# main.net
KiCad netlist of a schematic drawn in EAGLE
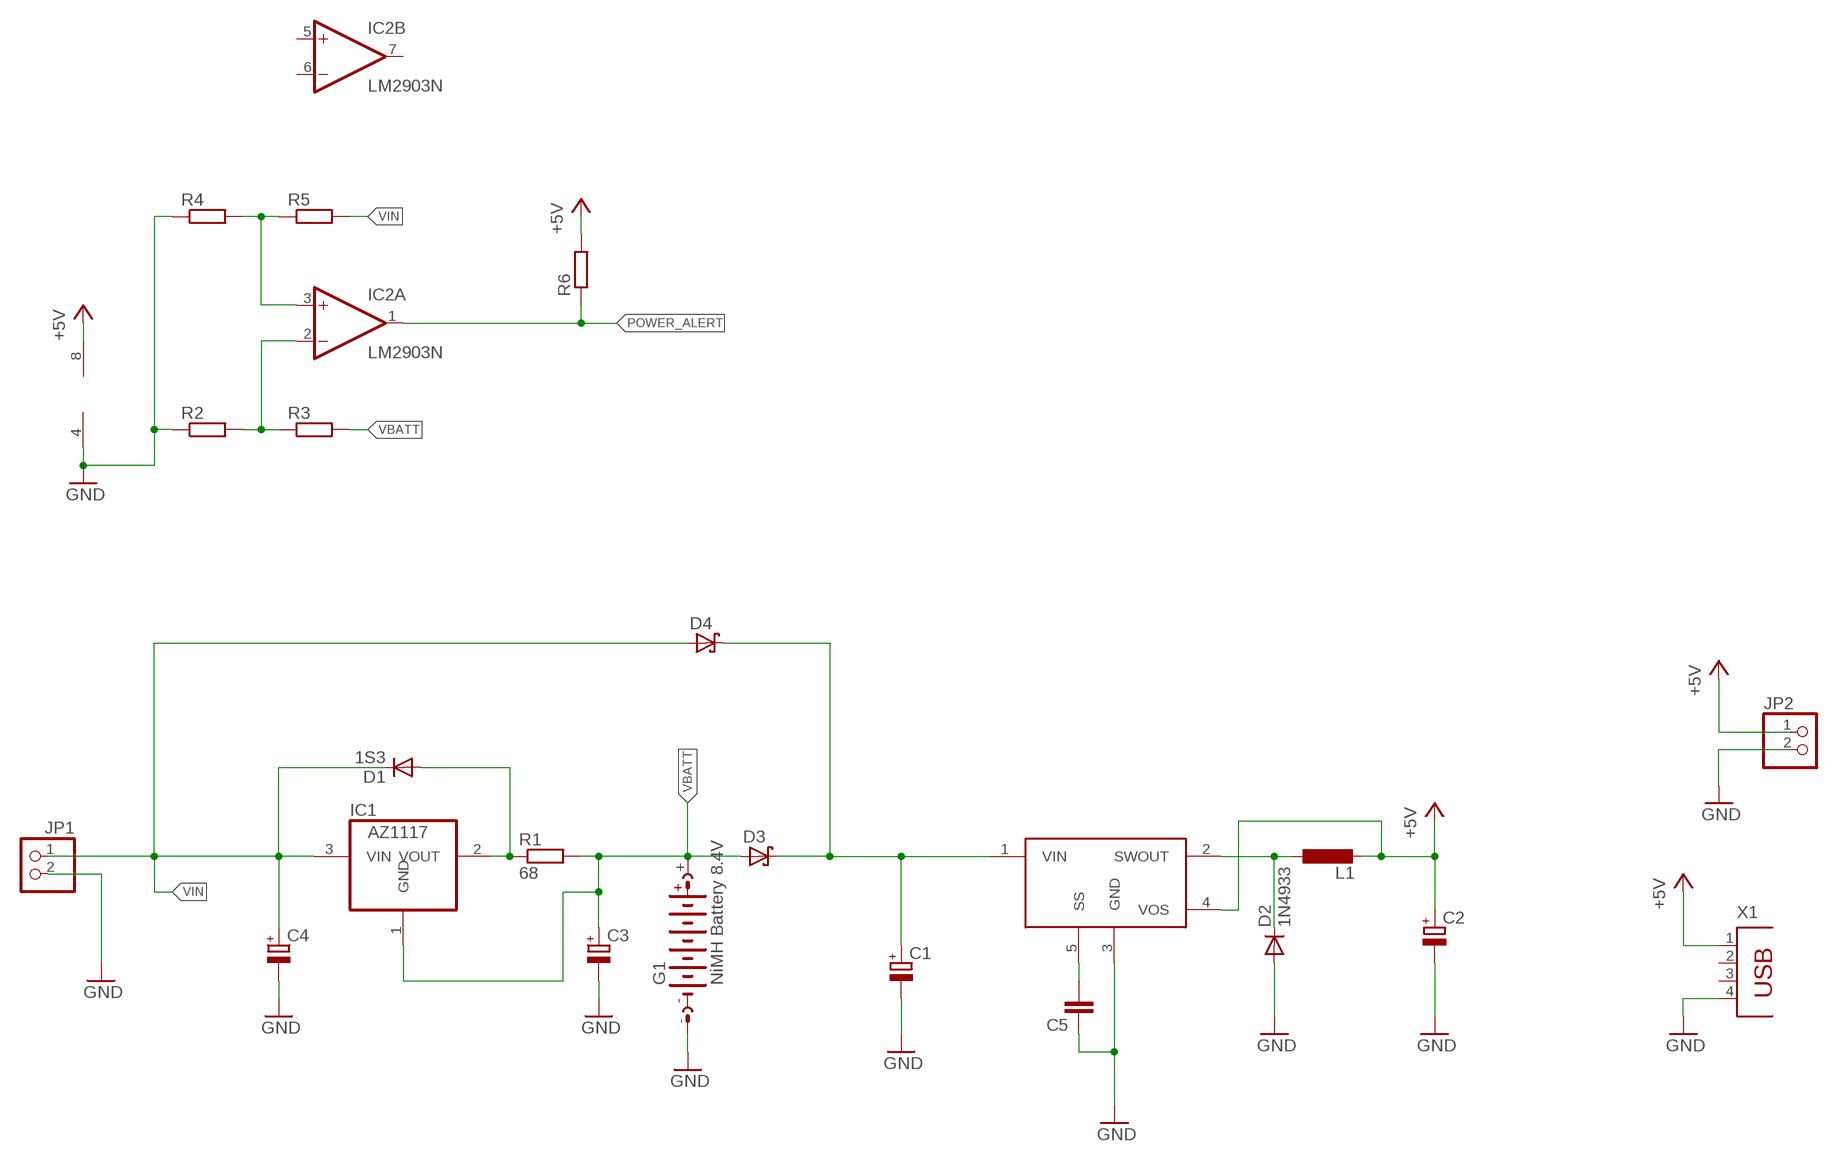
[diagram p0: schematic, sheet 1]

(export (version "E")
  (design (tool "Eeschema 10.0.6"))
  (components
    (comp (ref "C1")
      (value "CPOL-EUE5-10.5")
      (footprint "eagle-import:E5-10,5")
      (libsource (lib "eagle-import") (part "CPOL-EUE5-10.5"))
    )
    (comp (ref "C2")
      (value "CPOL-EUE5-10.5")
      (footprint "eagle-import:E5-10,5")
      (libsource (lib "eagle-import") (part "CPOL-EUE5-10.5"))
    )
    (comp (ref "C3")
      (value "CPOL-EUE5-10.5")
      (footprint "eagle-import:E5-10,5")
      (libsource (lib "eagle-import") (part "CPOL-EUE5-10.5"))
    )
    (comp (ref "C4")
      (value "CPOL-EUE5-10.5")
      (footprint "eagle-import:E5-10,5")
      (libsource (lib "eagle-import") (part "CPOL-EUE5-10.5"))
    )
    (comp (ref "C5")
      (value "C-EUC0603K")
      (footprint "eagle-import:C0603K")
      (libsource (lib "eagle-import") (part "C-EUC0603K"))
    )
    (comp (ref "D1")
      (value "1S3")
      (footprint "eagle-import:DO41-10")
      (libsource (lib "eagle-import") (part "1N4004"))
    )
    (comp (ref "D2")
      (value "1N4933")
      (footprint "eagle-import:DO41-10")
      (libsource (lib "eagle-import") (part "1N4933"))
    )
    (comp (ref "D3")
      (value "SCHOTTKY-DIODEC4111-15")
      (footprint "eagle-import:C4111-15")
      (libsource (lib "eagle-import") (part "SCHOTTKY-DIODEC4111-15"))
    )
    (comp (ref "D4")
      (value "SCHOTTKY-DIODEC4111-15")
      (footprint "eagle-import:C4111-15")
      (libsource (lib "eagle-import") (part "SCHOTTKY-DIODEC4111-15"))
    )
    (comp (ref "G1")
      (value "NiMH Battery 8.4V")
      (footprint "eagle-import:AB9V")
      (libsource (lib "eagle-import") (part "AB9V"))
    )
    (comp (ref "IC1")
      (value "AZ1117")
      (footprint "eagle-import:SOT223")
      (fields (field (name "MPN") "REG1117"))
      (libsource (lib "eagle-import") (part "REG1117"))
    )
    (comp (ref "IC2")
      (value "LM2903N")
      (footprint "eagle-import:DIL08")
      (libsource (lib "eagle-import") (part "LM2903N"))
    )
    (comp (ref "JP1")
      (value "PINHD-1X2")
      (footprint "eagle-import:1X02")
      (libsource (lib "eagle-import") (part "PINHD-1X2"))
    )
    (comp (ref "JP2")
      (value "PINHD-1X2")
      (footprint "eagle-import:1X02")
      (libsource (lib "eagle-import") (part "PINHD-1X2"))
    )
    (comp (ref "L1")
      (value "L-EU0207/10")
      (footprint "eagle-import:0207_10")
      (libsource (lib "eagle-import") (part "L-EU0207/10"))
    )
    (comp (ref "R1")
      (value "68")
      (footprint "eagle-import:0207_12")
      (libsource (lib "eagle-import") (part "R-EU_0207/12"))
    )
    (comp (ref "R2")
      (value "R-EU_R0603")
      (footprint "eagle-import:R0603")
      (libsource (lib "eagle-import") (part "R-EU_R0603"))
    )
    (comp (ref "R3")
      (value "R-EU_R0603")
      (footprint "eagle-import:R0603")
      (libsource (lib "eagle-import") (part "R-EU_R0603"))
    )
    (comp (ref "R4")
      (value "R-EU_R0603")
      (footprint "eagle-import:R0603")
      (libsource (lib "eagle-import") (part "R-EU_R0603"))
    )
    (comp (ref "R5")
      (value "R-EU_R0603")
      (footprint "eagle-import:R0603")
      (libsource (lib "eagle-import") (part "R-EU_R0603"))
    )
    (comp (ref "R6")
      (value "R-EU_R0603")
      (footprint "eagle-import:R0603")
      (libsource (lib "eagle-import") (part "R-EU_R0603"))
    )
    (comp (ref "U$1")
      (value "SI-8050S")
      (footprint "eagle-import:TO220-5")
      (libsource (lib "eagle-import") (part "SI-8050S"))
    )
    (comp (ref "X1")
      (value "PN87520")
      (footprint "eagle-import:PN87520")
      (libsource (lib "eagle-import") (part "PN87520"))
    )
  )
  (nets
    (net (code "1") (name "+5V") (class "Default")
      (node (ref "C2") (pin "+") (pinfunction "+_+") (pintype "passive"))
      (node (ref "IC2") (pin "8") (pinfunction "V+_8") (pintype "power_in"))
      (node (ref "JP2") (pin "1") (pinfunction "1_1") (pintype "passive"))
      (node (ref "L1") (pin "2") (pinfunction "2_2") (pintype "passive"))
      (node (ref "R6") (pin "2") (pinfunction "2_2") (pintype "passive"))
      (node (ref "U$1") (pin "4") (pinfunction "VOS_4") (pintype "bidirectional"))
      (node (ref "X1") (pin "1") (pinfunction "1_1") (pintype "passive"))
    )
    (net (code "2") (name "GND") (class "Default")
      (node (ref "C1") (pin "-") (pinfunction "-_-") (pintype "passive"))
      (node (ref "C2") (pin "-") (pinfunction "-_-") (pintype "passive"))
      (node (ref "C3") (pin "-") (pinfunction "-_-") (pintype "passive"))
      (node (ref "C4") (pin "-") (pinfunction "-_-") (pintype "passive"))
      (node (ref "C5") (pin "1") (pinfunction "1_1") (pintype "passive"))
      (node (ref "D2") (pin "A") (pinfunction "A_A") (pintype "passive"))
      (node (ref "G1") (pin "-") (pinfunction "-_-") (pintype "passive"))
      (node (ref "IC2") (pin "4") (pinfunction "V-_4") (pintype "power_in"))
      (node (ref "JP1") (pin "2") (pinfunction "2_2") (pintype "passive"))
      (node (ref "JP2") (pin "2") (pinfunction "2_2") (pintype "passive"))
      (node (ref "R2") (pin "1") (pinfunction "1_1") (pintype "passive"))
      (node (ref "R4") (pin "1") (pinfunction "1_1") (pintype "passive"))
      (node (ref "U$1") (pin "3") (pinfunction "GND_3") (pintype "bidirectional"))
      (node (ref "X1") (pin "4") (pinfunction "4_4") (pintype "passive"))
    )
    (net (code "3") (name "Net-(IC1-VOUT)") (class "Default")
      (node (ref "D1") (pin "A") (pinfunction "A_A") (pintype "passive"))
      (node (ref "IC1") (pin "2") (pinfunction "VOUT_2") (pintype "output"))
      (node (ref "R1") (pin "1") (pinfunction "1_1") (pintype "passive"))
    )
    (net (code "4") (name "Net-(IC2A-+IN)") (class "Default")
      (node (ref "IC2") (pin "3") (pinfunction "+IN_3") (pintype "input"))
      (node (ref "R4") (pin "2") (pinfunction "2_2") (pintype "passive"))
      (node (ref "R5") (pin "1") (pinfunction "1_1") (pintype "passive"))
    )
    (net (code "5") (name "Net-(IC2A--IN)") (class "Default")
      (node (ref "IC2") (pin "2") (pinfunction "-IN_2") (pintype "input"))
      (node (ref "R2") (pin "2") (pinfunction "2_2") (pintype "passive"))
      (node (ref "R3") (pin "1") (pinfunction "1_1") (pintype "passive"))
    )
    (net (code "6") (name "Net-(U$1-SS)") (class "Default")
      (node (ref "C5") (pin "2") (pinfunction "2_2") (pintype "passive"))
      (node (ref "U$1") (pin "5") (pinfunction "SS_5") (pintype "bidirectional"))
    )
    (net (code "7") (name "Net-(U$1-SWOUT)") (class "Default")
      (node (ref "D2") (pin "C") (pinfunction "C_C") (pintype "passive"))
      (node (ref "L1") (pin "1") (pinfunction "1_1") (pintype "passive"))
      (node (ref "U$1") (pin "2") (pinfunction "SWOUT_2") (pintype "bidirectional"))
    )
    (net (code "8") (name "Net-(U$1-VIN)") (class "Default")
      (node (ref "C1") (pin "+") (pinfunction "+_+") (pintype "passive"))
      (node (ref "D3") (pin "C") (pinfunction "C_C") (pintype "passive"))
      (node (ref "D4") (pin "C") (pinfunction "C_C") (pintype "passive"))
      (node (ref "U$1") (pin "1") (pinfunction "VIN_1") (pintype "bidirectional"))
    )
    (net (code "9") (name "POWER_ALERT") (class "Default")
      (node (ref "IC2") (pin "1") (pinfunction "OUT_1") (pintype "output"))
      (node (ref "R6") (pin "1") (pinfunction "1_1") (pintype "passive"))
    )
    (net (code "10") (name "VBATT") (class "Default")
      (node (ref "C3") (pin "+") (pinfunction "+_+") (pintype "passive"))
      (node (ref "D3") (pin "A") (pinfunction "A_A") (pintype "passive"))
      (node (ref "G1") (pin "+") (pinfunction "+_+") (pintype "passive"))
      (node (ref "IC1") (pin "1") (pinfunction "GND_1") (pintype "power_in"))
      (node (ref "R1") (pin "2") (pinfunction "2_2") (pintype "passive"))
      (node (ref "R3") (pin "2") (pinfunction "2_2") (pintype "passive"))
    )
    (net (code "11") (name "VIN") (class "Default")
      (node (ref "C4") (pin "+") (pinfunction "+_+") (pintype "passive"))
      (node (ref "D1") (pin "C") (pinfunction "C_C") (pintype "passive"))
      (node (ref "D4") (pin "A") (pinfunction "A_A") (pintype "passive"))
      (node (ref "IC1") (pin "3") (pinfunction "VIN_3") (pintype "input"))
      (node (ref "JP1") (pin "1") (pinfunction "1_1") (pintype "passive"))
      (node (ref "R5") (pin "2") (pinfunction "2_2") (pintype "passive"))
    )
    (net (code "12") (name "unconnected-(IC2B-+IN-Pad5)") (class "Default")
      (node (ref "IC2") (pin "5") (pinfunction "+IN_5") (pintype "input"))
    )
    (net (code "13") (name "unconnected-(IC2B--IN-Pad6)") (class "Default")
      (node (ref "IC2") (pin "6") (pinfunction "-IN_6") (pintype "input"))
    )
    (net (code "14") (name "unconnected-(IC2B-OUT-Pad7)") (class "Default")
      (node (ref "IC2") (pin "7") (pinfunction "OUT_7") (pintype "output"))
    )
    (net (code "15") (name "unconnected-(X1-Pad2)") (class "Default")
      (node (ref "X1") (pin "2") (pinfunction "2_2") (pintype "passive"))
    )
    (net (code "16") (name "unconnected-(X1-Pad3)") (class "Default")
      (node (ref "X1") (pin "3") (pinfunction "3_3") (pintype "passive"))
    )
  )
)
